# MySpot_Limit_Switch.net
KiCad netlist of a schematic drawn in EasyEDA
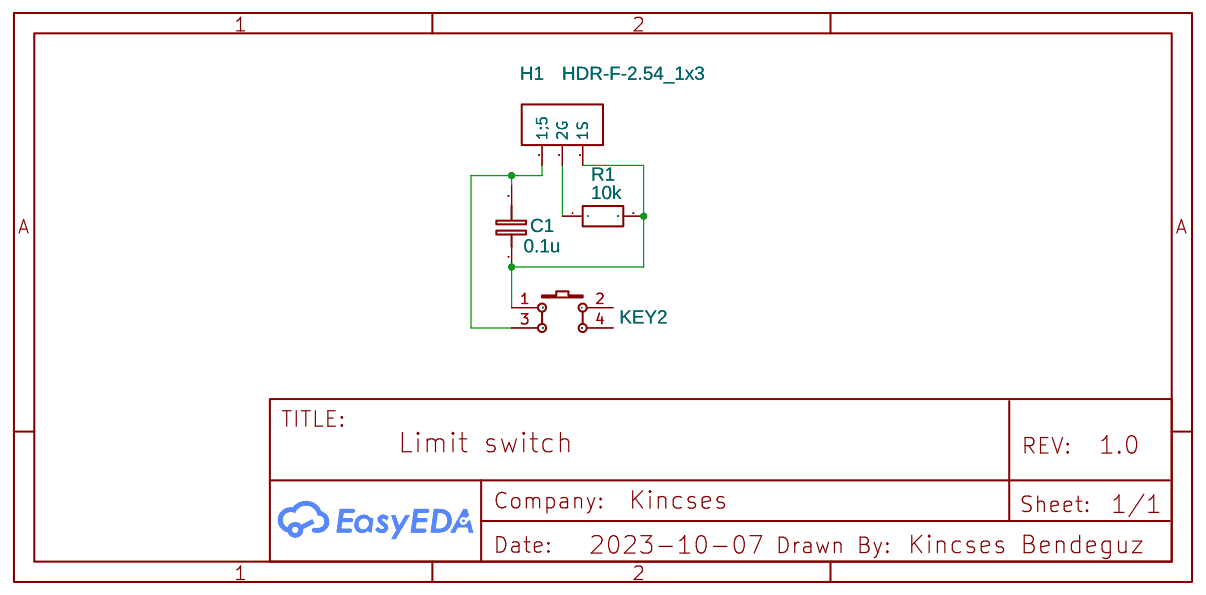
[diagram p0: schematic sheet]

(export (version "E")
  (design (tool "Eeschema 10.0.6"))
  (components
    (comp (ref "C1") (value "0.1u") (libsource (lib "") (part "C_RAD-0.1_EU")))
    (comp (ref "H1") (value "HDR-F-2.54_1x3") (libsource (lib "") (part "HDR-F-2.54_1x3")))
    (comp (ref "KEY2")
      (value "K4-12×12_TH")
      (fields (field (name "Manufacturer Part") "K2-1103DP-M4SW-04") (field (name "Manufacturer") "韩国韩荣"))
      (libsource (lib "") (part "K4-12×12_TH"))
    )
    (comp (ref "R1") (value "10k") (libsource (lib "") (part "R_0805_EU")))
  )
  (nets
    (net (code "1") (name "Net-(H1-1;5)") (class "Default")
      (node (ref "C1") (pin "2") (pinfunction "2_2") (pintype "unspecified"))
      (node (ref "H1") (pin "1") (pinfunction "1;5_1") (pintype "input"))
      (node (ref "KEY2") (pin "3") (pinfunction "1_3") (pintype "unspecified"))
    )
    (net (code "2") (name "Net-(H1-1S)") (class "Default")
      (node (ref "C1") (pin "1") (pinfunction "1_1") (pintype "unspecified"))
      (node (ref "H1") (pin "3") (pinfunction "1S_3") (pintype "input"))
      (node (ref "KEY2") (pin "1") (pinfunction "2_1") (pintype "unspecified"))
      (node (ref "R1") (pin "2") (pinfunction "2_2") (pintype "unspecified"))
    )
    (net (code "3") (name "Net-(H1-2G)") (class "Default")
      (node (ref "H1") (pin "2") (pinfunction "2G_2") (pintype "input"))
      (node (ref "R1") (pin "1") (pinfunction "1_1") (pintype "unspecified"))
    )
    (net (code "4") (name "unconnected-(KEY2-3-Pad4)") (class "Default")
      (node (ref "KEY2") (pin "4") (pinfunction "3_4") (pintype "unspecified"))
    )
    (net (code "5") (name "unconnected-(KEY2-4-Pad2)") (class "Default")
      (node (ref "KEY2") (pin "2") (pinfunction "4_2") (pintype "unspecified"))
    )
  )
)
